# Top.net
KiCad netlist of a schematic drawn in Altium Designer
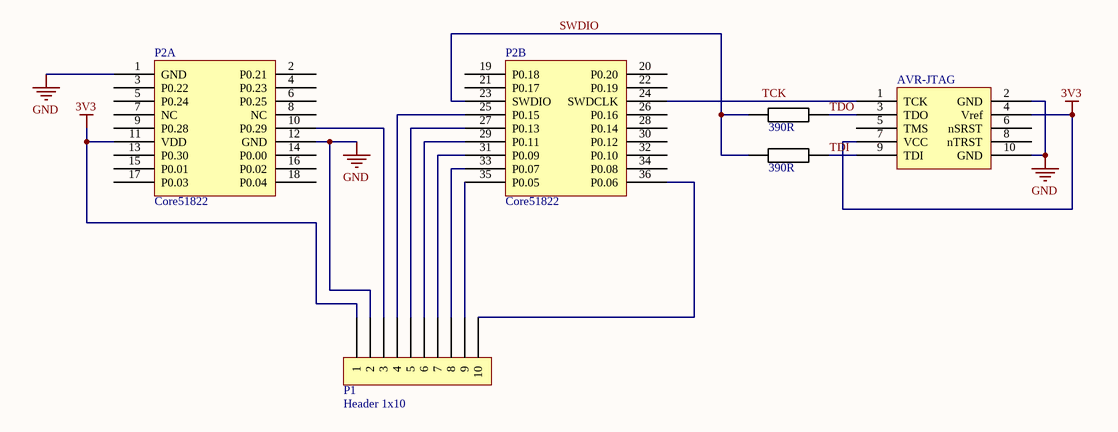
[diagram p0: Top.SchDoc]

(export (version "E")
  (design (tool "Eeschema 10.0.6"))
  (components
    (comp (ref "AVR-JTAG")
      (value "AVR Style")
      (footprint "Header 2x5 IDC-10S")
      (libsource (lib "Headers") (part "Header JTAG AVR"))
    )
    (comp (ref "P1")
      (value "Header 1x10")
      (footprint "Header 1x10 male")
      (libsource (lib "Headers") (part "Header 1x10"))
    )
    (comp (ref "P2")
      (value "Core51822")
      (footprint "Core51822")
      (libsource (lib "Modules") (part "Core51822_2"))
    )
    (comp (ref "RH-R1")
      (value "390R")
      (footprint "R 0805 / 2012 wide")
      (libsource (lib "Core51822-related") (part "Resistor"))
    )
    (comp (ref "RH-R2")
      (value "390R")
      (footprint "R 0805 / 2012 wide")
      (libsource (lib "Core51822-related") (part "Resistor"))
    )
  )
  (nets
    (net (code "1") (name "/SWDIO") (class "Default")
      (node (ref "P2") (pin "23") (pinfunction "SWDIO_23") (pintype "passive"))
      (node (ref "RH-R1") (pin "2") (pinfunction "2_2") (pintype "passive"))
      (node (ref "RH-R2") (pin "2") (pinfunction "2_2") (pintype "passive"))
    )
    (net (code "2") (name "/TCK") (class "Default")
      (node (ref "AVR-JTAG") (pin "1") (pinfunction "TCK_1") (pintype "passive"))
      (node (ref "P2") (pin "24") (pinfunction "SWDCLK_24") (pintype "passive"))
    )
    (net (code "3") (name "/TDI") (class "Default")
      (node (ref "AVR-JTAG") (pin "9") (pinfunction "TDI_9") (pintype "passive"))
      (node (ref "RH-R2") (pin "1") (pinfunction "1_1") (pintype "passive"))
    )
    (net (code "4") (name "/TDO") (class "Default")
      (node (ref "AVR-JTAG") (pin "3") (pinfunction "TDO_3") (pintype "passive"))
      (node (ref "RH-R1") (pin "1") (pinfunction "1_1") (pintype "passive"))
    )
    (net (code "5") (name "3V3") (class "Default")
      (node (ref "AVR-JTAG") (pin "4") (pinfunction "Vref_4") (pintype "passive"))
      (node (ref "AVR-JTAG") (pin "7") (pinfunction "VCC_7") (pintype "passive"))
      (node (ref "P1") (pin "1") (pinfunction "1_1") (pintype "passive"))
      (node (ref "P2") (pin "11") (pinfunction "VDD_11") (pintype "passive"))
    )
    (net (code "6") (name "GND") (class "Default")
      (node (ref "AVR-JTAG") (pin "10") (pinfunction "GND_10") (pintype "passive"))
      (node (ref "AVR-JTAG") (pin "2") (pinfunction "GND_2") (pintype "passive"))
      (node (ref "P1") (pin "2") (pinfunction "2_2") (pintype "passive"))
      (node (ref "P2") (pin "1") (pinfunction "GND_1") (pintype "passive"))
      (node (ref "P2") (pin "12") (pinfunction "GND_12") (pintype "passive"))
    )
    (net (code "7") (name "Net-(P2A-P0.29)") (class "Default")
      (node (ref "P1") (pin "3") (pinfunction "3_3") (pintype "passive"))
      (node (ref "P2") (pin "10") (pinfunction "P0.29_10") (pintype "passive"))
    )
    (net (code "8") (name "Net-(P2B-P0.05)") (class "Default")
      (node (ref "P1") (pin "9") (pinfunction "9_9") (pintype "passive"))
      (node (ref "P2") (pin "35") (pinfunction "P0.05_35") (pintype "passive"))
    )
    (net (code "9") (name "Net-(P2B-P0.06)") (class "Default")
      (node (ref "P1") (pin "10") (pinfunction "10_10") (pintype "passive"))
      (node (ref "P2") (pin "36") (pinfunction "P0.06_36") (pintype "passive"))
    )
    (net (code "10") (name "Net-(P2B-P0.07)") (class "Default")
      (node (ref "P1") (pin "8") (pinfunction "8_8") (pintype "passive"))
      (node (ref "P2") (pin "33") (pinfunction "P0.07_33") (pintype "passive"))
    )
    (net (code "11") (name "Net-(P2B-P0.09)") (class "Default")
      (node (ref "P1") (pin "7") (pinfunction "7_7") (pintype "passive"))
      (node (ref "P2") (pin "31") (pinfunction "P0.09_31") (pintype "passive"))
    )
    (net (code "12") (name "Net-(P2B-P0.11)") (class "Default")
      (node (ref "P1") (pin "6") (pinfunction "6_6") (pintype "passive"))
      (node (ref "P2") (pin "29") (pinfunction "P0.11_29") (pintype "passive"))
    )
    (net (code "13") (name "Net-(P2B-P0.13)") (class "Default")
      (node (ref "P1") (pin "5") (pinfunction "5_5") (pintype "passive"))
      (node (ref "P2") (pin "27") (pinfunction "P0.13_27") (pintype "passive"))
    )
    (net (code "14") (name "Net-(P2B-P0.15)") (class "Default")
      (node (ref "P1") (pin "4") (pinfunction "4_4") (pintype "passive"))
      (node (ref "P2") (pin "25") (pinfunction "P0.15_25") (pintype "passive"))
    )
    (net (code "15") (name "unconnected-(AVR-JTAG-TMS-Pad5)") (class "Default")
      (node (ref "AVR-JTAG") (pin "5") (pinfunction "TMS_5") (pintype "passive"))
    )
    (net (code "16") (name "unconnected-(AVR-JTAG-nSRST-Pad6)") (class "Default")
      (node (ref "AVR-JTAG") (pin "6") (pinfunction "nSRST_6") (pintype "passive"))
    )
    (net (code "17") (name "unconnected-(AVR-JTAG-nTRST-Pad8)") (class "Default")
      (node (ref "AVR-JTAG") (pin "8") (pinfunction "nTRST_8") (pintype "passive"))
    )
    (net (code "18") (name "unconnected-(P2A-NC-Pad7)") (class "Default")
      (node (ref "P2") (pin "7") (pinfunction "NC_7") (pintype "passive"))
    )
    (net (code "19") (name "unconnected-(P2A-NC-Pad8)") (class "Default")
      (node (ref "P2") (pin "8") (pinfunction "NC_8") (pintype "passive"))
    )
    (net (code "20") (name "unconnected-(P2A-P0.00-Pad14)") (class "Default")
      (node (ref "P2") (pin "14") (pinfunction "P0.00_14") (pintype "passive"))
    )
    (net (code "21") (name "unconnected-(P2A-P0.01-Pad15)") (class "Default")
      (node (ref "P2") (pin "15") (pinfunction "P0.01_15") (pintype "passive"))
    )
    (net (code "22") (name "unconnected-(P2A-P0.02-Pad16)") (class "Default")
      (node (ref "P2") (pin "16") (pinfunction "P0.02_16") (pintype "passive"))
    )
    (net (code "23") (name "unconnected-(P2A-P0.03-Pad17)") (class "Default")
      (node (ref "P2") (pin "17") (pinfunction "P0.03_17") (pintype "passive"))
    )
    (net (code "24") (name "unconnected-(P2A-P0.04-Pad18)") (class "Default")
      (node (ref "P2") (pin "18") (pinfunction "P0.04_18") (pintype "passive"))
    )
    (net (code "25") (name "unconnected-(P2A-P0.21-Pad2)") (class "Default")
      (node (ref "P2") (pin "2") (pinfunction "P0.21_2") (pintype "passive"))
    )
    (net (code "26") (name "unconnected-(P2A-P0.22-Pad3)") (class "Default")
      (node (ref "P2") (pin "3") (pinfunction "P0.22_3") (pintype "passive"))
    )
    (net (code "27") (name "unconnected-(P2A-P0.23-Pad4)") (class "Default")
      (node (ref "P2") (pin "4") (pinfunction "P0.23_4") (pintype "passive"))
    )
    (net (code "28") (name "unconnected-(P2A-P0.24-Pad5)") (class "Default")
      (node (ref "P2") (pin "5") (pinfunction "P0.24_5") (pintype "passive"))
    )
    (net (code "29") (name "unconnected-(P2A-P0.25-Pad6)") (class "Default")
      (node (ref "P2") (pin "6") (pinfunction "P0.25_6") (pintype "passive"))
    )
    (net (code "30") (name "unconnected-(P2A-P0.28-Pad9)") (class "Default")
      (node (ref "P2") (pin "9") (pinfunction "P0.28_9") (pintype "passive"))
    )
    (net (code "31") (name "unconnected-(P2A-P0.30-Pad13)") (class "Default")
      (node (ref "P2") (pin "13") (pinfunction "P0.30_13") (pintype "passive"))
    )
    (net (code "32") (name "unconnected-(P2B-P0.08-Pad34)") (class "Default")
      (node (ref "P2") (pin "34") (pinfunction "P0.08_34") (pintype "passive"))
    )
    (net (code "33") (name "unconnected-(P2B-P0.10-Pad32)") (class "Default")
      (node (ref "P2") (pin "32") (pinfunction "P0.10_32") (pintype "passive"))
    )
    (net (code "34") (name "unconnected-(P2B-P0.12-Pad30)") (class "Default")
      (node (ref "P2") (pin "30") (pinfunction "P0.12_30") (pintype "passive"))
    )
    (net (code "35") (name "unconnected-(P2B-P0.14-Pad28)") (class "Default")
      (node (ref "P2") (pin "28") (pinfunction "P0.14_28") (pintype "passive"))
    )
    (net (code "36") (name "unconnected-(P2B-P0.16-Pad26)") (class "Default")
      (node (ref "P2") (pin "26") (pinfunction "P0.16_26") (pintype "passive"))
    )
    (net (code "37") (name "unconnected-(P2B-P0.17-Pad21)") (class "Default")
      (node (ref "P2") (pin "21") (pinfunction "P0.17_21") (pintype "power_in"))
    )
    (net (code "38") (name "unconnected-(P2B-P0.18-Pad19)") (class "Default")
      (node (ref "P2") (pin "19") (pinfunction "P0.18_19") (pintype "passive"))
    )
    (net (code "39") (name "unconnected-(P2B-P0.19-Pad22)") (class "Default")
      (node (ref "P2") (pin "22") (pinfunction "P0.19_22") (pintype "passive"))
    )
    (net (code "40") (name "unconnected-(P2B-P0.20-Pad20)") (class "Default")
      (node (ref "P2") (pin "20") (pinfunction "P0.20_20") (pintype "passive"))
    )
  )
)
